# 7segGates.net
KiCad netlist of a schematic drawn in EAGLE
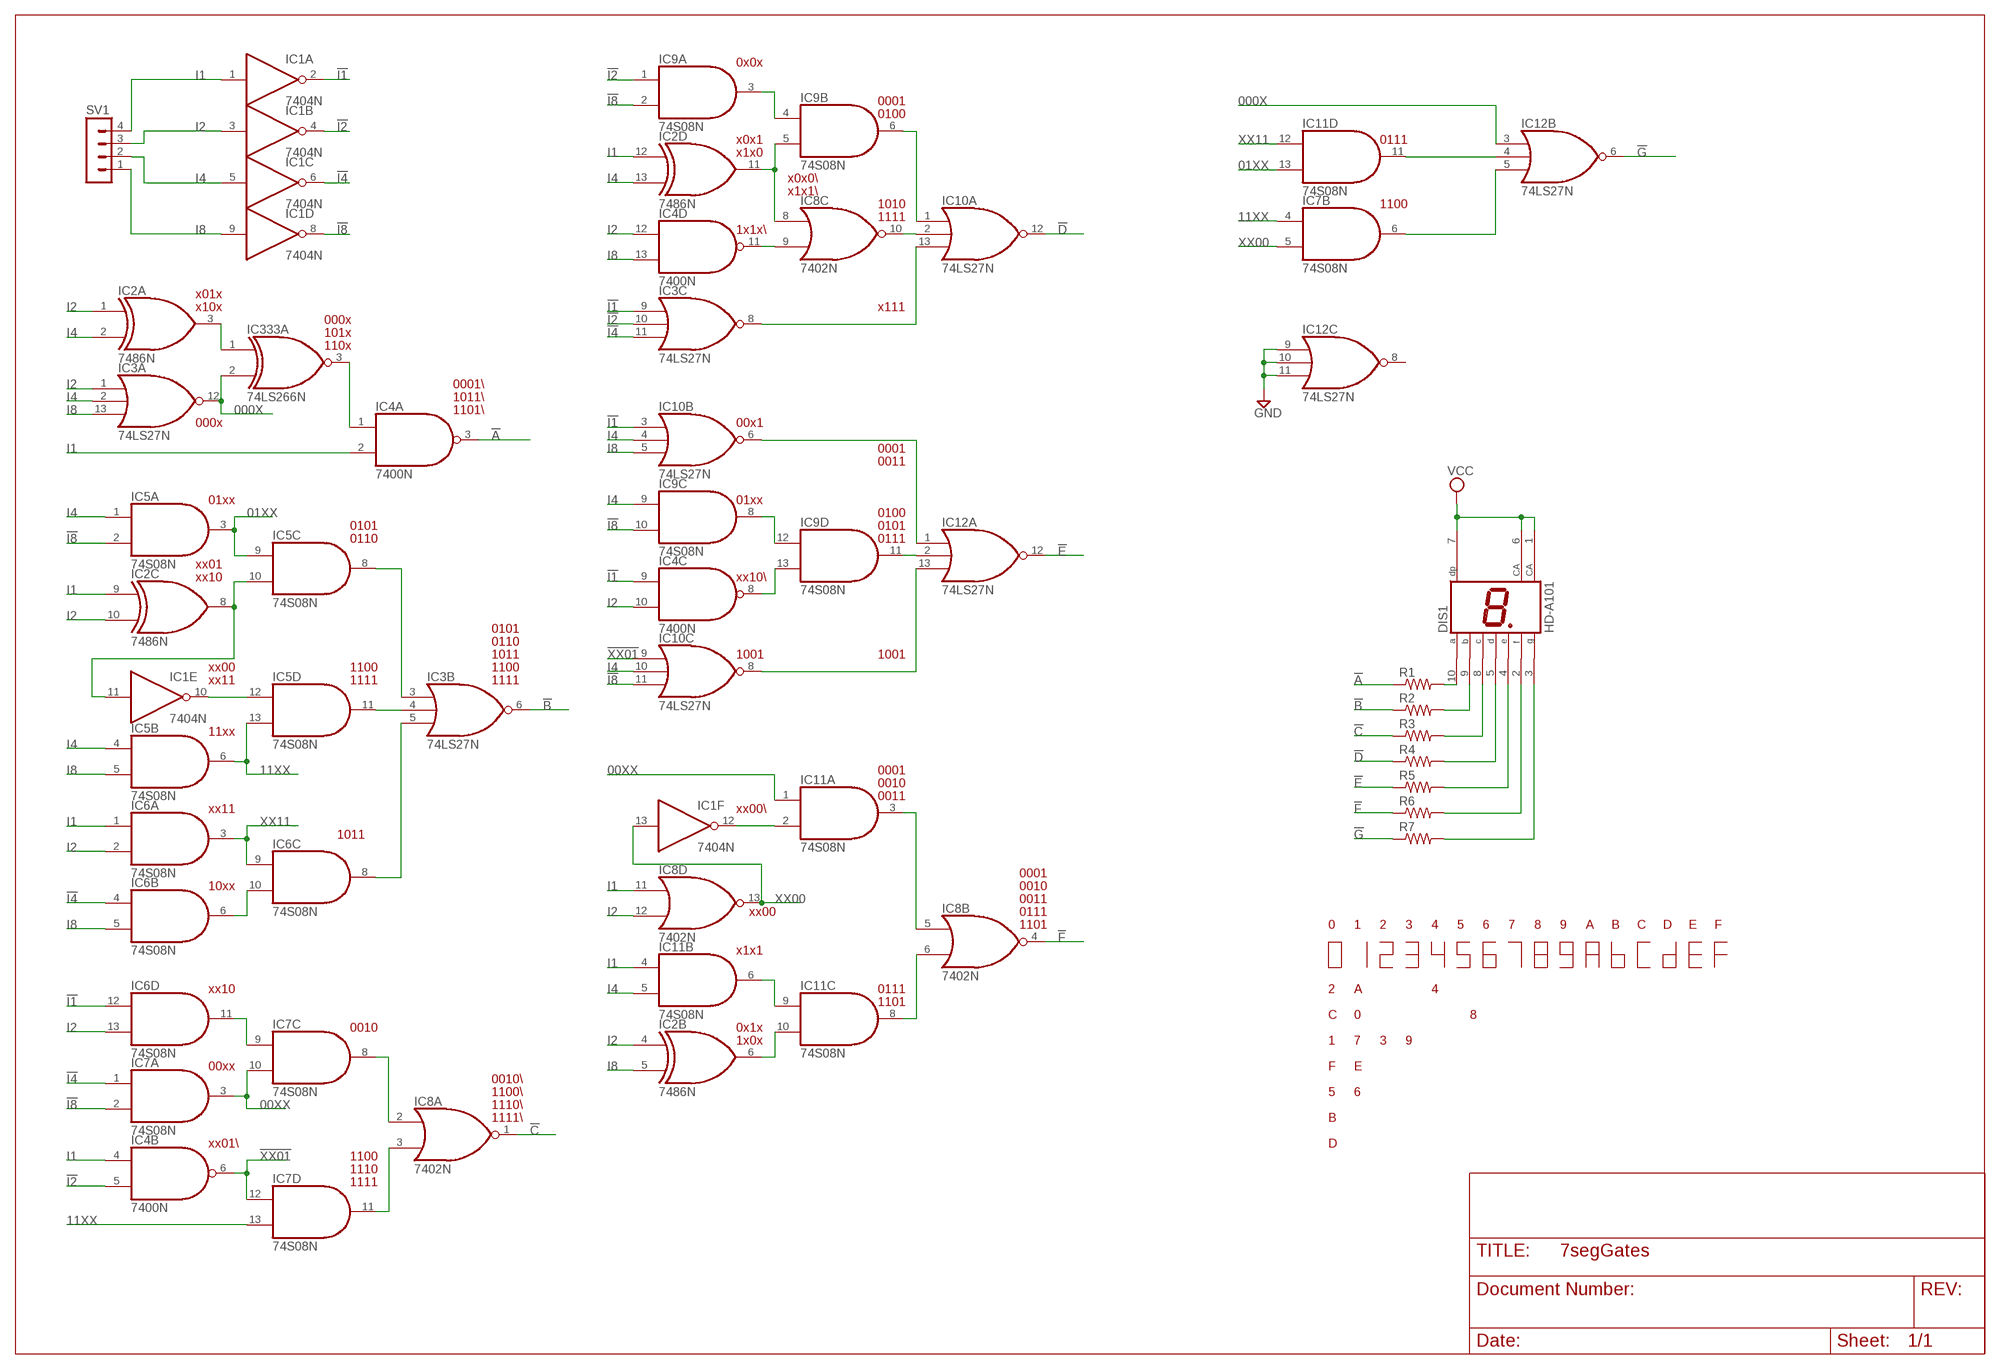
[diagram p0: schematic, sheet 1]

(export (version "E")
  (design (tool "Eeschema 10.0.6"))
  (components
    (comp (ref "DIS1")
      (value "HD-A101")
      (footprint "eagle-import:HDSP-A")
      (libsource (lib "eagle-import") (part "HD-A101"))
    )
    (comp (ref "IC1")
      (value "7404N")
      (footprint "eagle-import:DIL14")
      (libsource (lib "eagle-import") (part "7404N"))
    )
    (comp (ref "IC2")
      (value "7486N")
      (footprint "eagle-import:DIL14")
      (libsource (lib "eagle-import") (part "7486N"))
    )
    (comp (ref "IC3")
      (value "74LS27N")
      (footprint "eagle-import:DIL14")
      (libsource (lib "eagle-import") (part "7427NLS"))
    )
    (comp (ref "IC4")
      (value "7400N")
      (footprint "eagle-import:DIL14")
      (libsource (lib "eagle-import") (part "7400N"))
    )
    (comp (ref "IC5")
      (value "74S08N")
      (footprint "eagle-import:DIL14")
      (libsource (lib "eagle-import") (part "7408NS"))
    )
    (comp (ref "IC6")
      (value "74S08N")
      (footprint "eagle-import:DIL14")
      (libsource (lib "eagle-import") (part "7408NS"))
    )
    (comp (ref "IC7")
      (value "74S08N")
      (footprint "eagle-import:DIL14")
      (libsource (lib "eagle-import") (part "7408NS"))
    )
    (comp (ref "IC8")
      (value "7402N")
      (footprint "eagle-import:DIL14")
      (libsource (lib "eagle-import") (part "7402N"))
    )
    (comp (ref "IC9")
      (value "74S08N")
      (footprint "eagle-import:DIL14")
      (libsource (lib "eagle-import") (part "7408NS"))
    )
    (comp (ref "IC10")
      (value "74LS27N")
      (footprint "eagle-import:DIL14")
      (libsource (lib "eagle-import") (part "7427NLS"))
    )
    (comp (ref "IC11")
      (value "74S08N")
      (footprint "eagle-import:DIL14")
      (libsource (lib "eagle-import") (part "7408NS"))
    )
    (comp (ref "IC12")
      (value "74LS27N")
      (footprint "eagle-import:DIL14")
      (libsource (lib "eagle-import") (part "7427NLS"))
    )
    (comp (ref "IC333")
      (value "74LS266N")
      (footprint "eagle-import:DIL14")
      (libsource (lib "eagle-import") (part "74266NLS"))
    )
    (comp (ref "R1")
      (value "R-US_0207/10")
      (footprint "eagle-import:0207_10")
      (libsource (lib "eagle-import") (part "R-US_0207/10"))
    )
    (comp (ref "R2")
      (value "R-US_0207/10")
      (footprint "eagle-import:0207_10")
      (libsource (lib "eagle-import") (part "R-US_0207/10"))
    )
    (comp (ref "R3")
      (value "R-US_0207/10")
      (footprint "eagle-import:0207_10")
      (libsource (lib "eagle-import") (part "R-US_0207/10"))
    )
    (comp (ref "R4")
      (value "R-US_0207/10")
      (footprint "eagle-import:0207_10")
      (libsource (lib "eagle-import") (part "R-US_0207/10"))
    )
    (comp (ref "R5")
      (value "R-US_0207/10")
      (footprint "eagle-import:0207_10")
      (libsource (lib "eagle-import") (part "R-US_0207/10"))
    )
    (comp (ref "R6")
      (value "R-US_0207/10")
      (footprint "eagle-import:0207_10")
      (libsource (lib "eagle-import") (part "R-US_0207/10"))
    )
    (comp (ref "R7")
      (value "R-US_0207/10")
      (footprint "eagle-import:0207_10")
      (libsource (lib "eagle-import") (part "R-US_0207/10"))
    )
    (comp (ref "SV1")
      (value "MA04-1")
      (footprint "eagle-import:MA04-1")
      (libsource (lib "eagle-import") (part "MA04-1"))
    )
  )
  (nets
    (net (code "1") (name "/000X") (class "Default")
      (node (ref "IC12") (pin "3") (pinfunction "I0_3") (pintype "input"))
      (node (ref "IC3") (pin "12") (pinfunction "O_12") (pintype "output"))
      (node (ref "IC333") (pin "2") (pinfunction "I1_2") (pintype "input"))
    )
    (net (code "2") (name "/00XX") (class "Default")
      (node (ref "IC11") (pin "1") (pinfunction "I0_1") (pintype "input"))
      (node (ref "IC7") (pin "10") (pinfunction "I1_10") (pintype "input"))
      (node (ref "IC7") (pin "3") (pinfunction "O_3") (pintype "output"))
    )
    (net (code "3") (name "/01XX") (class "Default")
      (node (ref "IC11") (pin "13") (pinfunction "I1_13") (pintype "input"))
      (node (ref "IC5") (pin "3") (pinfunction "O_3") (pintype "output"))
      (node (ref "IC5") (pin "9") (pinfunction "I0_9") (pintype "input"))
    )
    (net (code "4") (name "/11XX") (class "Default")
      (node (ref "IC5") (pin "13") (pinfunction "I1_13") (pintype "input"))
      (node (ref "IC5") (pin "6") (pinfunction "O_6") (pintype "output"))
      (node (ref "IC7") (pin "13") (pinfunction "I1_13") (pintype "input"))
      (node (ref "IC7") (pin "4") (pinfunction "I0_4") (pintype "input"))
    )
    (net (code "5") (name "/I1") (class "Default")
      (node (ref "IC1") (pin "1") (pinfunction "I_1") (pintype "input"))
      (node (ref "IC11") (pin "4") (pinfunction "I0_4") (pintype "input"))
      (node (ref "IC2") (pin "12") (pinfunction "I0_12") (pintype "input"))
      (node (ref "IC2") (pin "9") (pinfunction "I0_9") (pintype "input"))
      (node (ref "IC4") (pin "2") (pinfunction "I1_2") (pintype "input"))
      (node (ref "IC4") (pin "4") (pinfunction "I0_4") (pintype "input"))
      (node (ref "IC6") (pin "1") (pinfunction "I0_1") (pintype "input"))
      (node (ref "IC8") (pin "11") (pinfunction "I0_11") (pintype "input"))
      (node (ref "SV1") (pin "4") (pinfunction "4_4") (pintype "passive"))
    )
    (net (code "6") (name "/I2") (class "Default")
      (node (ref "IC1") (pin "3") (pinfunction "I_3") (pintype "input"))
      (node (ref "IC2") (pin "1") (pinfunction "I0_1") (pintype "input"))
      (node (ref "IC2") (pin "10") (pinfunction "I1_10") (pintype "input"))
      (node (ref "IC2") (pin "4") (pinfunction "I0_4") (pintype "input"))
      (node (ref "IC3") (pin "1") (pinfunction "I0_1") (pintype "input"))
      (node (ref "IC4") (pin "10") (pinfunction "I1_10") (pintype "input"))
      (node (ref "IC4") (pin "12") (pinfunction "I0_12") (pintype "input"))
      (node (ref "IC6") (pin "13") (pinfunction "I1_13") (pintype "input"))
      (node (ref "IC6") (pin "2") (pinfunction "I1_2") (pintype "input"))
      (node (ref "IC8") (pin "12") (pinfunction "I1_12") (pintype "input"))
      (node (ref "SV1") (pin "3") (pinfunction "3_3") (pintype "passive"))
    )
    (net (code "7") (name "/I4") (class "Default")
      (node (ref "IC1") (pin "5") (pinfunction "I_5") (pintype "input"))
      (node (ref "IC10") (pin "10") (pinfunction "I1_10") (pintype "input"))
      (node (ref "IC10") (pin "4") (pinfunction "I1_4") (pintype "input"))
      (node (ref "IC11") (pin "5") (pinfunction "I1_5") (pintype "input"))
      (node (ref "IC2") (pin "13") (pinfunction "I1_13") (pintype "input"))
      (node (ref "IC2") (pin "2") (pinfunction "I1_2") (pintype "input"))
      (node (ref "IC3") (pin "2") (pinfunction "I1_2") (pintype "input"))
      (node (ref "IC5") (pin "1") (pinfunction "I0_1") (pintype "input"))
      (node (ref "IC5") (pin "4") (pinfunction "I0_4") (pintype "input"))
      (node (ref "IC9") (pin "9") (pinfunction "I0_9") (pintype "input"))
      (node (ref "SV1") (pin "2") (pinfunction "2_2") (pintype "passive"))
    )
    (net (code "8") (name "/I8") (class "Default")
      (node (ref "IC1") (pin "9") (pinfunction "I_9") (pintype "input"))
      (node (ref "IC10") (pin "5") (pinfunction "I2_5") (pintype "input"))
      (node (ref "IC2") (pin "5") (pinfunction "I1_5") (pintype "input"))
      (node (ref "IC3") (pin "13") (pinfunction "I2_13") (pintype "input"))
      (node (ref "IC4") (pin "13") (pinfunction "I1_13") (pintype "input"))
      (node (ref "IC5") (pin "5") (pinfunction "I1_5") (pintype "input"))
      (node (ref "IC6") (pin "5") (pinfunction "I1_5") (pintype "input"))
      (node (ref "SV1") (pin "1") (pinfunction "1_1") (pintype "passive"))
    )
    (net (code "9") (name "/XX00") (class "Default")
      (node (ref "IC1") (pin "13") (pinfunction "I_13") (pintype "input"))
      (node (ref "IC7") (pin "5") (pinfunction "I1_5") (pintype "input"))
      (node (ref "IC8") (pin "13") (pinfunction "O_13") (pintype "output"))
    )
    (net (code "10") (name "/XX11") (class "Default")
      (node (ref "IC11") (pin "12") (pinfunction "I0_12") (pintype "input"))
      (node (ref "IC6") (pin "3") (pinfunction "O_3") (pintype "output"))
      (node (ref "IC6") (pin "9") (pinfunction "I0_9") (pintype "input"))
    )
    (net (code "11") (name "/~{A}") (class "Default")
      (node (ref "IC4") (pin "3") (pinfunction "O_3") (pintype "output"))
      (node (ref "R1") (pin "1") (pinfunction "1_1") (pintype "passive"))
    )
    (net (code "12") (name "/~{B}") (class "Default")
      (node (ref "IC3") (pin "6") (pinfunction "O_6") (pintype "output"))
      (node (ref "R2") (pin "1") (pinfunction "1_1") (pintype "passive"))
    )
    (net (code "13") (name "/~{C}") (class "Default")
      (node (ref "IC8") (pin "1") (pinfunction "O_1") (pintype "output"))
      (node (ref "R3") (pin "1") (pinfunction "1_1") (pintype "passive"))
    )
    (net (code "14") (name "/~{D}") (class "Default")
      (node (ref "IC10") (pin "12") (pinfunction "O_12") (pintype "output"))
      (node (ref "R4") (pin "1") (pinfunction "1_1") (pintype "passive"))
    )
    (net (code "15") (name "/~{E}") (class "Default")
      (node (ref "IC12") (pin "12") (pinfunction "O_12") (pintype "output"))
      (node (ref "R5") (pin "1") (pinfunction "1_1") (pintype "passive"))
    )
    (net (code "16") (name "/~{F}") (class "Default")
      (node (ref "IC8") (pin "4") (pinfunction "O_4") (pintype "output"))
      (node (ref "R6") (pin "1") (pinfunction "1_1") (pintype "passive"))
    )
    (net (code "17") (name "/~{G}") (class "Default")
      (node (ref "IC12") (pin "6") (pinfunction "O_6") (pintype "output"))
      (node (ref "R7") (pin "1") (pinfunction "1_1") (pintype "passive"))
    )
    (net (code "18") (name "/~{I1}") (class "Default")
      (node (ref "IC1") (pin "2") (pinfunction "O_2") (pintype "output"))
      (node (ref "IC10") (pin "3") (pinfunction "I0_3") (pintype "input"))
      (node (ref "IC3") (pin "9") (pinfunction "I0_9") (pintype "input"))
      (node (ref "IC4") (pin "9") (pinfunction "I0_9") (pintype "input"))
      (node (ref "IC6") (pin "12") (pinfunction "I0_12") (pintype "input"))
    )
    (net (code "19") (name "/~{I2}") (class "Default")
      (node (ref "IC1") (pin "4") (pinfunction "O_4") (pintype "output"))
      (node (ref "IC3") (pin "10") (pinfunction "I1_10") (pintype "input"))
      (node (ref "IC4") (pin "5") (pinfunction "I1_5") (pintype "input"))
      (node (ref "IC9") (pin "1") (pinfunction "I0_1") (pintype "input"))
    )
    (net (code "20") (name "/~{I4}") (class "Default")
      (node (ref "IC1") (pin "6") (pinfunction "O_6") (pintype "output"))
      (node (ref "IC3") (pin "11") (pinfunction "I2_11") (pintype "input"))
      (node (ref "IC6") (pin "4") (pinfunction "I0_4") (pintype "input"))
      (node (ref "IC7") (pin "1") (pinfunction "I0_1") (pintype "input"))
    )
    (net (code "21") (name "/~{I8}") (class "Default")
      (node (ref "IC1") (pin "8") (pinfunction "O_8") (pintype "output"))
      (node (ref "IC10") (pin "11") (pinfunction "I2_11") (pintype "input"))
      (node (ref "IC5") (pin "2") (pinfunction "I1_2") (pintype "input"))
      (node (ref "IC7") (pin "2") (pinfunction "I1_2") (pintype "input"))
      (node (ref "IC9") (pin "10") (pinfunction "I1_10") (pintype "input"))
      (node (ref "IC9") (pin "2") (pinfunction "I1_2") (pintype "input"))
    )
    (net (code "22") (name "/~{XX01}") (class "Default")
      (node (ref "IC10") (pin "9") (pinfunction "I0_9") (pintype "input"))
      (node (ref "IC4") (pin "6") (pinfunction "O_6") (pintype "output"))
      (node (ref "IC7") (pin "12") (pinfunction "I0_12") (pintype "input"))
    )
    (net (code "23") (name "GND") (class "Default")
      (node (ref "IC12") (pin "10") (pinfunction "I1_10") (pintype "input"))
      (node (ref "IC12") (pin "11") (pinfunction "I2_11") (pintype "input"))
      (node (ref "IC12") (pin "9") (pinfunction "I0_9") (pintype "input"))
    )
    (net (code "24") (name "Net-(DIS1-A)") (class "Default")
      (node (ref "DIS1") (pin "10") (pinfunction "A_10") (pintype "passive"))
      (node (ref "R1") (pin "2") (pinfunction "2_2") (pintype "passive"))
    )
    (net (code "25") (name "Net-(DIS1-B)") (class "Default")
      (node (ref "DIS1") (pin "9") (pinfunction "B_9") (pintype "passive"))
      (node (ref "R2") (pin "2") (pinfunction "2_2") (pintype "passive"))
    )
    (net (code "26") (name "Net-(DIS1-C)") (class "Default")
      (node (ref "DIS1") (pin "8") (pinfunction "C_8") (pintype "passive"))
      (node (ref "R3") (pin "2") (pinfunction "2_2") (pintype "passive"))
    )
    (net (code "27") (name "Net-(DIS1-D)") (class "Default")
      (node (ref "DIS1") (pin "5") (pinfunction "D_5") (pintype "passive"))
      (node (ref "R4") (pin "2") (pinfunction "2_2") (pintype "passive"))
    )
    (net (code "28") (name "Net-(DIS1-E)") (class "Default")
      (node (ref "DIS1") (pin "4") (pinfunction "E_4") (pintype "passive"))
      (node (ref "R5") (pin "2") (pinfunction "2_2") (pintype "passive"))
    )
    (net (code "29") (name "Net-(DIS1-F)") (class "Default")
      (node (ref "DIS1") (pin "2") (pinfunction "F_2") (pintype "passive"))
      (node (ref "R6") (pin "2") (pinfunction "2_2") (pintype "passive"))
    )
    (net (code "30") (name "Net-(DIS1-G)") (class "Default")
      (node (ref "DIS1") (pin "3") (pinfunction "G_3") (pintype "passive"))
      (node (ref "R7") (pin "2") (pinfunction "2_2") (pintype "passive"))
    )
    (net (code "31") (name "Net-(IC1E-I)") (class "Default")
      (node (ref "IC1") (pin "11") (pinfunction "I_11") (pintype "input"))
      (node (ref "IC2") (pin "8") (pinfunction "O_8") (pintype "output"))
      (node (ref "IC5") (pin "10") (pinfunction "I1_10") (pintype "input"))
    )
    (net (code "32") (name "Net-(IC1E-O)") (class "Default")
      (node (ref "IC1") (pin "10") (pinfunction "O_10") (pintype "output"))
      (node (ref "IC5") (pin "12") (pinfunction "I0_12") (pintype "input"))
    )
    (net (code "33") (name "Net-(IC2A-O)") (class "Default")
      (node (ref "IC2") (pin "3") (pinfunction "O_3") (pintype "output"))
      (node (ref "IC333") (pin "1") (pinfunction "I0_1") (pintype "input"))
    )
    (net (code "34") (name "Net-(IC2D-O)") (class "Default")
      (node (ref "IC2") (pin "11") (pinfunction "O_11") (pintype "output"))
      (node (ref "IC8") (pin "8") (pinfunction "I0_8") (pintype "input"))
      (node (ref "IC9") (pin "5") (pinfunction "I1_5") (pintype "input"))
    )
    (net (code "35") (name "Net-(IC3B-I0)") (class "Default")
      (node (ref "IC3") (pin "3") (pinfunction "I0_3") (pintype "input"))
      (node (ref "IC5") (pin "8") (pinfunction "O_8") (pintype "output"))
    )
    (net (code "36") (name "Net-(IC3B-I1)") (class "Default")
      (node (ref "IC3") (pin "4") (pinfunction "I1_4") (pintype "input"))
      (node (ref "IC5") (pin "11") (pinfunction "O_11") (pintype "output"))
    )
    (net (code "37") (name "Net-(IC3B-I2)") (class "Default")
      (node (ref "IC3") (pin "5") (pinfunction "I2_5") (pintype "input"))
      (node (ref "IC6") (pin "8") (pinfunction "O_8") (pintype "output"))
    )
    (net (code "38") (name "Net-(IC4C-O)") (class "Default")
      (node (ref "IC4") (pin "8") (pinfunction "O_8") (pintype "output"))
      (node (ref "IC9") (pin "13") (pinfunction "I1_13") (pintype "input"))
    )
    (net (code "39") (name "Net-(IC4D-O)") (class "Default")
      (node (ref "IC4") (pin "11") (pinfunction "O_11") (pintype "output"))
      (node (ref "IC8") (pin "9") (pinfunction "I1_9") (pintype "input"))
    )
    (net (code "40") (name "Net-(IC6B-O)") (class "Default")
      (node (ref "IC6") (pin "10") (pinfunction "I1_10") (pintype "input"))
      (node (ref "IC6") (pin "6") (pinfunction "O_6") (pintype "output"))
    )
    (net (code "41") (name "Net-(IC6D-O)") (class "Default")
      (node (ref "IC6") (pin "11") (pinfunction "O_11") (pintype "output"))
      (node (ref "IC7") (pin "9") (pinfunction "I0_9") (pintype "input"))
    )
    (net (code "42") (name "Net-(IC7C-O)") (class "Default")
      (node (ref "IC7") (pin "8") (pinfunction "O_8") (pintype "output"))
      (node (ref "IC8") (pin "2") (pinfunction "I0_2") (pintype "input"))
    )
    (net (code "43") (name "Net-(IC7D-O)") (class "Default")
      (node (ref "IC7") (pin "11") (pinfunction "O_11") (pintype "output"))
      (node (ref "IC8") (pin "3") (pinfunction "I1_3") (pintype "input"))
    )
    (net (code "44") (name "Net-(IC9A-O)") (class "Default")
      (node (ref "IC9") (pin "3") (pinfunction "O_3") (pintype "output"))
      (node (ref "IC9") (pin "4") (pinfunction "I0_4") (pintype "input"))
    )
    (net (code "45") (name "Net-(IC9C-O)") (class "Default")
      (node (ref "IC9") (pin "12") (pinfunction "I0_12") (pintype "input"))
      (node (ref "IC9") (pin "8") (pinfunction "O_8") (pintype "output"))
    )
    (net (code "46") (name "Net-(IC10A-I0)") (class "Default")
      (node (ref "IC10") (pin "1") (pinfunction "I0_1") (pintype "input"))
      (node (ref "IC9") (pin "6") (pinfunction "O_6") (pintype "output"))
    )
    (net (code "47") (name "Net-(IC10A-I1)") (class "Default")
      (node (ref "IC10") (pin "2") (pinfunction "I1_2") (pintype "input"))
      (node (ref "IC8") (pin "10") (pinfunction "O_10") (pintype "output"))
    )
    (net (code "48") (name "Net-(IC10A-I2)") (class "Default")
      (node (ref "IC10") (pin "13") (pinfunction "I2_13") (pintype "input"))
      (node (ref "IC3") (pin "8") (pinfunction "O_8") (pintype "output"))
    )
    (net (code "49") (name "Net-(IC10B-O)") (class "Default")
      (node (ref "IC10") (pin "6") (pinfunction "O_6") (pintype "output"))
      (node (ref "IC12") (pin "1") (pinfunction "I0_1") (pintype "input"))
    )
    (net (code "50") (name "Net-(IC10C-O)") (class "Default")
      (node (ref "IC10") (pin "8") (pinfunction "O_8") (pintype "output"))
      (node (ref "IC12") (pin "13") (pinfunction "I2_13") (pintype "input"))
    )
    (net (code "51") (name "Net-(IC11A-I1)") (class "Default")
      (node (ref "IC1") (pin "12") (pinfunction "O_12") (pintype "output"))
      (node (ref "IC11") (pin "2") (pinfunction "I1_2") (pintype "input"))
    )
    (net (code "52") (name "Net-(IC11A-O)") (class "Default")
      (node (ref "IC11") (pin "3") (pinfunction "O_3") (pintype "output"))
      (node (ref "IC8") (pin "5") (pinfunction "I0_5") (pintype "input"))
    )
    (net (code "53") (name "Net-(IC11B-O)") (class "Default")
      (node (ref "IC11") (pin "6") (pinfunction "O_6") (pintype "output"))
      (node (ref "IC11") (pin "9") (pinfunction "I0_9") (pintype "input"))
    )
    (net (code "54") (name "Net-(IC11C-I1)") (class "Default")
      (node (ref "IC11") (pin "10") (pinfunction "I1_10") (pintype "input"))
      (node (ref "IC2") (pin "6") (pinfunction "O_6") (pintype "output"))
    )
    (net (code "55") (name "Net-(IC11C-O)") (class "Default")
      (node (ref "IC11") (pin "8") (pinfunction "O_8") (pintype "output"))
      (node (ref "IC8") (pin "6") (pinfunction "I1_6") (pintype "input"))
    )
    (net (code "56") (name "Net-(IC11D-O)") (class "Default")
      (node (ref "IC11") (pin "11") (pinfunction "O_11") (pintype "output"))
      (node (ref "IC12") (pin "4") (pinfunction "I1_4") (pintype "input"))
    )
    (net (code "57") (name "Net-(IC12A-I1)") (class "Default")
      (node (ref "IC12") (pin "2") (pinfunction "I1_2") (pintype "input"))
      (node (ref "IC9") (pin "11") (pinfunction "O_11") (pintype "output"))
    )
    (net (code "58") (name "Net-(IC12B-I2)") (class "Default")
      (node (ref "IC12") (pin "5") (pinfunction "I2_5") (pintype "input"))
      (node (ref "IC7") (pin "6") (pinfunction "O_6") (pintype "output"))
    )
    (net (code "59") (name "Net-(IC333A-O)") (class "Default")
      (node (ref "IC333") (pin "3") (pinfunction "O_3") (pintype "open_collector"))
      (node (ref "IC4") (pin "1") (pinfunction "I0_1") (pintype "input"))
    )
    (net (code "60") (name "VCC") (class "Default")
      (node (ref "DIS1") (pin "1") (pinfunction "CA_1") (pintype "passive"))
      (node (ref "DIS1") (pin "6") (pinfunction "CA_6") (pintype "passive"))
      (node (ref "DIS1") (pin "7") (pinfunction "DP_7") (pintype "passive"))
    )
    (net (code "61") (name "unconnected-(IC12C-O-Pad8)") (class "Default")
      (node (ref "IC12") (pin "8") (pinfunction "O_8") (pintype "output"))
    )
  )
)
